# SAML21_Xplained_Pro_Target_MCU.net
KiCad netlist of a schematic drawn in Altium Designer
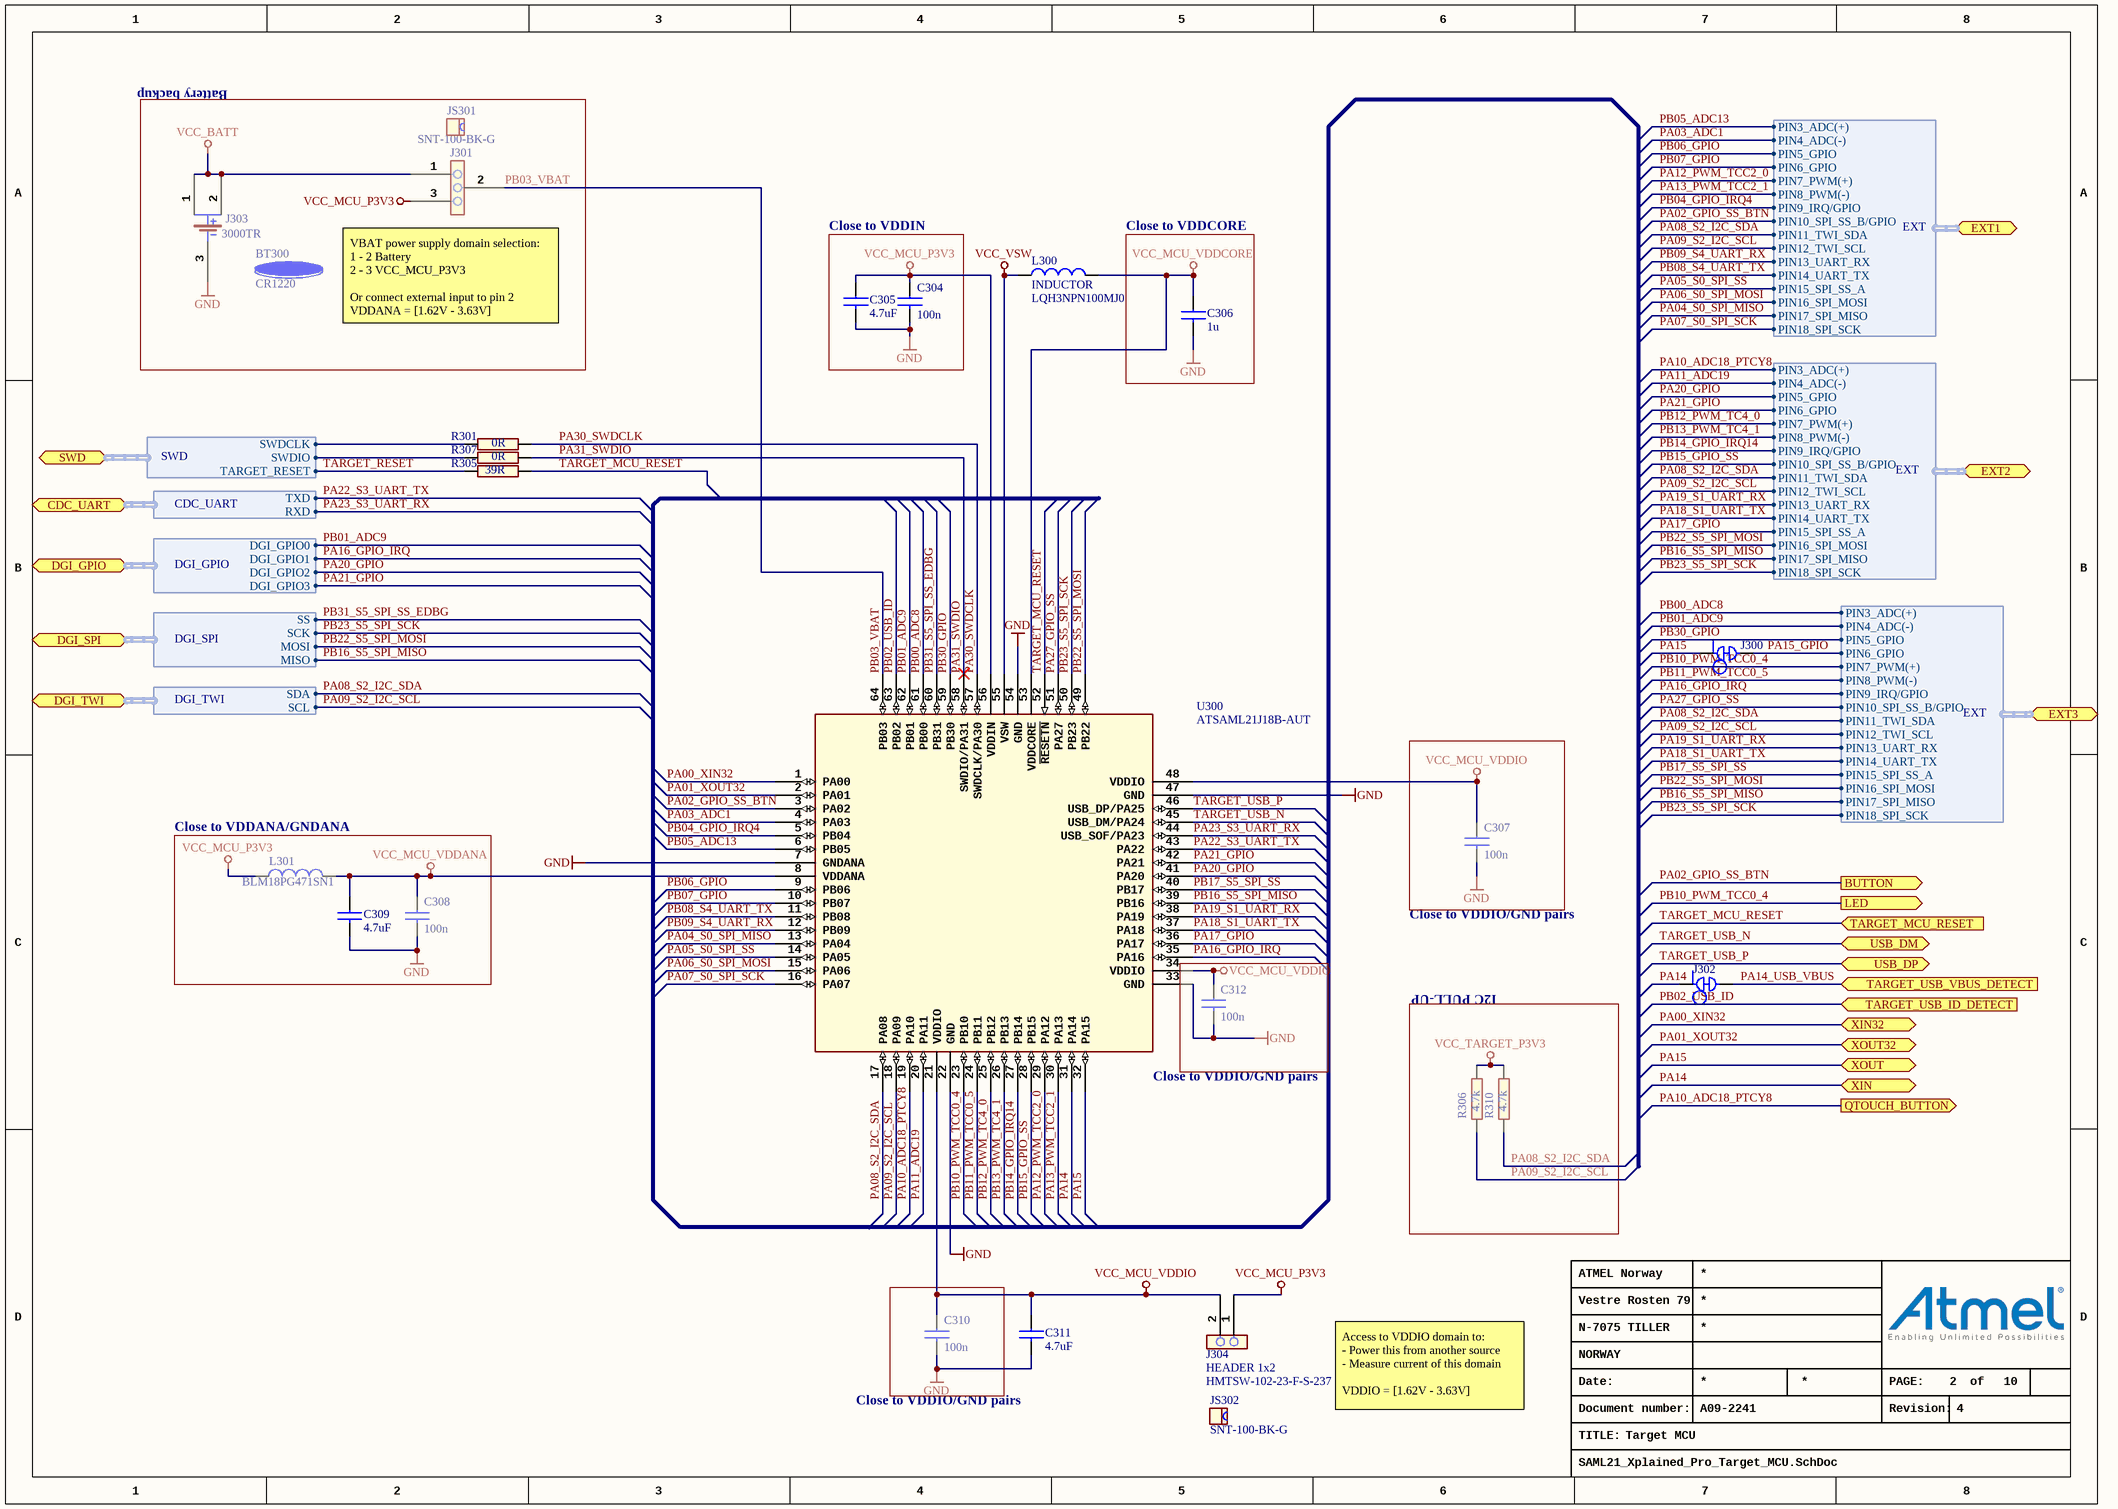
[diagram p0: SAML21_Xplained_Pro_Target_MCU.SchDoc]

(export (version "E")
  (design (tool "Eeschema 10.0.6"))
  (components
    (comp (ref "BT300")
      (value "CR1220")
      (footprint "AP9-00125")
      (description "CR1220 Lithium coin-cell battery")
      (fields (field (name "MANUFACTURER") "Panasonic") (field (name "Comment") "COIN-CELL"))
      (libsource (lib "AltiumDbLib") (part "COIN-CELL"))
    )
    (comp (ref "C304")
      (value "100n")
      (footprint "AP1-00053")
      (description "Ceramic capacitor, SMD 0402, X7R, 16V, +/-10%")
      (fields (field (name "TOLERANCE") "16V, +/-10%") (field (name "MANUFACTURER") "Kemet"))
      (libsource (lib "AltiumDbLib") (part "CAP-NONPOL"))
    )
    (comp (ref "C305")
      (value "4.7uF")
      (footprint "AP1-00117")
      (description "Ceramic capacitor, SMD 0603, X5R, 10V, 10% (de31036)")
      (fields (field (name "TOLERANCE") "10%") (field (name "MANUFACTURER") "tdk"))
      (libsource (lib "AltiumDbLib") (part "CAP-NONPOL"))
    )
    (comp (ref "C306")
      (value "1u")
      (footprint "AP1-00053")
      (description "Ceramic capacitor, SMD 0402, X5R, 6.3V, +/-10% (de26942)")
      (fields (field (name "TOLERANCE") "+/-10%") (field (name "MANUFACTURER") "Kemet"))
      (libsource (lib "AltiumDbLib") (part "CAP-NONPOL"))
    )
    (comp (ref "C307")
      (value "100n")
      (footprint "AP1-00053")
      (description "Ceramic capacitor, SMD 0402, X7R, 16V, +/-10%")
      (fields (field (name "TOLERANCE") "16V, +/-10%") (field (name "MANUFACTURER") "Kemet"))
      (libsource (lib "AltiumDbLib") (part "CAP-NONPOL"))
    )
    (comp (ref "C308")
      (value "100n")
      (footprint "AP1-00053")
      (description "Ceramic capacitor, SMD 0402, X7R, 16V, +/-10%")
      (fields (field (name "TOLERANCE") "16V, +/-10%") (field (name "MANUFACTURER") "Kemet"))
      (libsource (lib "AltiumDbLib") (part "CAP-NONPOL"))
    )
    (comp (ref "C309")
      (value "4.7uF")
      (footprint "AP1-00117")
      (description "Ceramic capacitor, SMD 0603, X5R, 10V, 10% (de31036)")
      (fields (field (name "TOLERANCE") "10%") (field (name "MANUFACTURER") "tdk"))
      (libsource (lib "AltiumDbLib") (part "CAP-NONPOL"))
    )
    (comp (ref "C310")
      (value "100n")
      (footprint "AP1-00053")
      (description "Ceramic capacitor, SMD 0402, X7R, 16V, +/-10%")
      (fields (field (name "TOLERANCE") "16V, +/-10%") (field (name "MANUFACTURER") "Kemet"))
      (libsource (lib "AltiumDbLib") (part "CAP-NONPOL"))
    )
    (comp (ref "C311")
      (value "4.7uF")
      (footprint "AP1-00117")
      (description "Ceramic capacitor, SMD 0603, X5R, 10V, 10% (de31036)")
      (fields (field (name "TOLERANCE") "10%") (field (name "MANUFACTURER") "tdk"))
      (libsource (lib "AltiumDbLib") (part "CAP-NONPOL"))
    )
    (comp (ref "C312")
      (value "100n")
      (footprint "AP1-00053")
      (description "Ceramic capacitor, SMD 0402, X7R, 16V, +/-10%")
      (fields (field (name "TOLERANCE") "16V, +/-10%") (field (name "MANUFACTURER") "Kemet"))
      (libsource (lib "AltiumDbLib") (part "CAP-NONPOL"))
    )
    (comp (ref "J300")
      (value "~")
      (footprint "AP9-00044")
      (description "Default closed SMD strap, 0603 size")
      (libsource (lib "AltiumDbLib") (part "SMD-STRAP_CLOSED"))
    )
    (comp (ref "J301")
      (value "Same as A08-1614 but with 1mm hole for optimal reflow soldering (no misalignment of the component)")
      (footprint "AP8-00745")
      (description "1x3 pin header, 2.54mm pitch, Pin-in-Paste THM, 1mm hole")
      (fields (field (name "MANUFACTURER") "SAMTEC") (field (name "MPN") "HMTSW-103-23-F-S-237"))
      (libsource (lib "AltiumDbLib") (part "HEADER 1x3"))
    )
    (comp (ref "J302")
      (value "~")
      (footprint "AP9-00044")
      (description "Default closed SMD strap, 0603 size")
      (libsource (lib "AltiumDbLib") (part "SMD-STRAP_CLOSED"))
    )
    (comp (ref "J303")
      (value "3000TR")
      (footprint "AP8-00313")
      (description "CR1220 Li-Ion coin-cell battery clip, SMD")
      (fields (field (name "MANUFACTURER") "Keystone Corp.") (field (name "Comment") "Elfa no: 69-525-01"))
      (libsource (lib "AltiumDbLib") (part "BATTERY_CLIP"))
    )
    (comp (ref "J304")
      (value "HEADER 1x2")
      (footprint "AP8-00733")
      (description "1x2 pin header, 2.54mm pitch, Pin-in-Paste THM")
      (fields
        (field (name "ALTIUM_VALUE") "HMTSW-102-23-F-S-237")
        (field (name "MANUFACTURER") "SAMTEC")
        (field (name "MPN") "HMTSW-102-23-F-S-237")
      )
      (libsource (lib "AltiumDbLib") (part "HEADER 1x2"))
    )
    (comp (ref "JS301")
      (value "SNT-100-BK-G")
      (footprint "AP8-00525")
      (description "Jumper cap for 2.54mm pinheader")
      (fields (field (name "MANUFACTURER") "SAMTEC"))
      (libsource (lib "AltiumDbLib") (part "JUMPER_CAP"))
    )
    (comp (ref "JS302")
      (value "SNT-100-BK-G")
      (footprint "AP8-00525")
      (description "Jumper cap for 2.54mm pinheader")
      (fields (field (name "MANUFACTURER") "SAMTEC"))
      (libsource (lib "AltiumDbLib") (part "JUMPER_CAP"))
    )
    (comp (ref "L300")
      (value "INDUCTOR")
      (footprint "AP3-00115")
      (description "10uH power inductor, Isat = 560mA , Itemp = 710mA, Rdc = 0.360ohm")
      (fields
        (field (name "ALTIUM_VALUE") "LQH3NPN100MJ0")
        (field (name "MANUFACTURER") "Murata")
        (field (name "MPN") "LQH3NPN100MJ0")
      )
      (libsource (lib "AltiumDbLib") (part "INDUCTOR"))
    )
    (comp (ref "L301")
      (value "BLM18PG471SN1")
      (footprint "AP3-00005")
      (description "SMD RF inductor 0603. Z=470Ohm (@100MHz), Max R(dc)=0.65Ohm, Max current=1A")
      (fields (field (name "TOLERANCE") "±25%") (field (name "MANUFACTURER") "Murata"))
      (libsource (lib "AltiumDbLib") (part "INDUCTOR"))
    )
    (comp (ref "R301")
      (value "0R")
      (footprint "AP2-00011")
      (description "RES 0.0 OHM 1/16W 0402 SMD")
      (fields (field (name "TOLERANCE") "1 %") (field (name "MANUFACTURER") "(n/a)"))
      (libsource (lib "") (part "R2_1"))
    )
    (comp (ref "R305")
      (value "39R")
      (footprint "AP2-00011")
      (description "Thick film resistor, SMD 0402, 1/16W, 1%")
      (fields (field (name "TOLERANCE") "1 %") (field (name "Comment") "R2"))
      (libsource (lib "") (part "R2_2"))
    )
    (comp (ref "R306")
      (value "4.7k")
      (footprint "AP2-00011")
      (description "Thick film resistor, SMD 0402, 1/16W, 1%")
      (fields (field (name "TOLERANCE") "1 %") (field (name "Comment") "R2"))
      (libsource (lib "AltiumDbLib") (part "R2"))
    )
    (comp (ref "R307")
      (value "0R")
      (footprint "AP2-00011")
      (description "RES 0.0 OHM 1/16W 0402 SMD")
      (fields (field (name "TOLERANCE") "1 %") (field (name "MANUFACTURER") "(n/a)"))
      (libsource (lib "") (part "R2_1"))
    )
    (comp (ref "R310")
      (value "4.7k")
      (footprint "AP2-00011")
      (description "Thick film resistor, SMD 0402, 1/16W, 1%")
      (fields (field (name "TOLERANCE") "1 %") (field (name "Comment") "R2"))
      (libsource (lib "AltiumDbLib") (part "R2"))
    )
    (comp (ref "U300")
      (value "ATSAML21J18B-AUT")
      (footprint "AP6-00173")
      (description "Atmel 32-bit RISC MCU 64pin")
      (fields (field (name "Comment") "TQFP64"))
      (libsource (lib "AltiumDbLib") (part "SAML21J_TQFP64"))
    )
  )
  (nets
    (net (code "7") (name "/PA00_XIN32") (class "Default")
      (node (ref "U300") (pin "1") (pinfunction "PA00_1") (pintype "bidirectional"))
    )
    (net (code "8") (name "/PA01_XOUT32") (class "Default")
      (node (ref "U300") (pin "2") (pinfunction "PA01_2") (pintype "bidirectional"))
    )
    (net (code "9") (name "/PA02_GPIO_SS_BTN") (class "Default")
      (node (ref "U300") (pin "3") (pinfunction "PA02_3") (pintype "bidirectional"))
    )
    (net (code "10") (name "/PA03_ADC1") (class "Default")
      (node (ref "U300") (pin "4") (pinfunction "PA03_4") (pintype "bidirectional"))
    )
    (net (code "11") (name "/PA04_S0_SPI_MISO") (class "Default")
      (node (ref "U300") (pin "13") (pinfunction "PA04_13") (pintype "bidirectional"))
    )
    (net (code "12") (name "/PA05_S0_SPI_SS") (class "Default")
      (node (ref "U300") (pin "14") (pinfunction "PA05_14") (pintype "bidirectional"))
    )
    (net (code "13") (name "/PA06_S0_SPI_MOSI") (class "Default")
      (node (ref "U300") (pin "15") (pinfunction "PA06_15") (pintype "bidirectional"))
    )
    (net (code "14") (name "/PA07_S0_SPI_SCK") (class "Default")
      (node (ref "U300") (pin "16") (pinfunction "PA07_16") (pintype "bidirectional"))
    )
    (net (code "15") (name "/PA08_S2_I2C_SDA") (class "Default")
      (node (ref "R310") (pin "1") (pinfunction "1_1") (pintype "passive"))
      (node (ref "U300") (pin "17") (pinfunction "PA08_17") (pintype "bidirectional"))
    )
    (net (code "16") (name "/PA09_S2_I2C_SCL") (class "Default")
      (node (ref "R306") (pin "1") (pinfunction "1_1") (pintype "passive"))
      (node (ref "U300") (pin "18") (pinfunction "PA09_18") (pintype "bidirectional"))
    )
    (net (code "17") (name "/PA10_ADC18_PTCY8") (class "Default")
      (node (ref "U300") (pin "19") (pinfunction "PA10_19") (pintype "bidirectional"))
    )
    (net (code "18") (name "/PA11_ADC19") (class "Default")
      (node (ref "U300") (pin "20") (pinfunction "PA11_20") (pintype "bidirectional"))
    )
    (net (code "19") (name "/PA12_PWM_TCC2_0") (class "Default")
      (node (ref "U300") (pin "29") (pinfunction "PA12_29") (pintype "bidirectional"))
    )
    (net (code "20") (name "/PA13_PWM_TCC2_1") (class "Default")
      (node (ref "U300") (pin "30") (pinfunction "PA13_30") (pintype "bidirectional"))
    )
    (net (code "21") (name "/PA14") (class "Default")
      (node (ref "J302") (pin "1") (pinfunction "1_1") (pintype "passive"))
      (node (ref "U300") (pin "31") (pinfunction "PA14_31") (pintype "bidirectional"))
    )
    (net (code "22") (name "/PA14_USB_VBUS") (class "Default")
      (node (ref "J302") (pin "2") (pinfunction "2_2") (pintype "passive"))
    )
    (net (code "23") (name "/PA15") (class "Default")
      (node (ref "J300") (pin "1") (pinfunction "1_1") (pintype "passive"))
      (node (ref "U300") (pin "32") (pinfunction "PA15_32") (pintype "bidirectional"))
    )
    (net (code "24") (name "/PA15_GPIO") (class "Default")
      (node (ref "J300") (pin "2") (pinfunction "2_2") (pintype "passive"))
    )
    (net (code "25") (name "/PA16_GPIO_IRQ") (class "Default")
      (node (ref "U300") (pin "35") (pinfunction "PA16_35") (pintype "bidirectional"))
    )
    (net (code "26") (name "/PA17_GPIO") (class "Default")
      (node (ref "U300") (pin "36") (pinfunction "PA17_36") (pintype "bidirectional"))
    )
    (net (code "27") (name "/PA18_S1_UART_TX") (class "Default")
      (node (ref "U300") (pin "37") (pinfunction "PA18_37") (pintype "bidirectional"))
    )
    (net (code "28") (name "/PA19_S1_UART_RX") (class "Default")
      (node (ref "U300") (pin "38") (pinfunction "PA19_38") (pintype "bidirectional"))
    )
    (net (code "29") (name "/PA20_GPIO") (class "Default")
      (node (ref "U300") (pin "41") (pinfunction "PA20_41") (pintype "bidirectional"))
    )
    (net (code "30") (name "/PA21_GPIO") (class "Default")
      (node (ref "U300") (pin "42") (pinfunction "PA21_42") (pintype "bidirectional"))
    )
    (net (code "31") (name "/PA22_S3_UART_TX") (class "Default")
      (node (ref "U300") (pin "43") (pinfunction "PA22_43") (pintype "bidirectional"))
    )
    (net (code "32") (name "/PA23_S3_UART_RX") (class "Default")
      (node (ref "U300") (pin "44") (pinfunction "USB_SOF/PA23_44") (pintype "bidirectional"))
    )
    (net (code "33") (name "/PA27_GPIO_SS") (class "Default")
      (node (ref "U300") (pin "51") (pinfunction "PA27_51") (pintype "bidirectional"))
    )
    (net (code "34") (name "/PA30_SWDCLK") (class "Default")
      (node (ref "R301") (pin "1") (pinfunction "1_1") (pintype "passive"))
      (node (ref "U300") (pin "57") (pinfunction "SWDCLK/PA30_57") (pintype "bidirectional"))
    )
    (net (code "35") (name "/PA31_SWDIO") (class "Default")
      (node (ref "R307") (pin "1") (pinfunction "1_1") (pintype "passive"))
      (node (ref "U300") (pin "58") (pinfunction "SWDIO/PA31_58") (pintype "bidirectional"))
    )
    (net (code "36") (name "/PB00_ADC8") (class "Default")
      (node (ref "U300") (pin "61") (pinfunction "PB00_61") (pintype "bidirectional"))
    )
    (net (code "37") (name "/PB01_ADC9") (class "Default")
      (node (ref "U300") (pin "62") (pinfunction "PB01_62") (pintype "bidirectional"))
    )
    (net (code "38") (name "/PB02_USB_ID") (class "Default")
      (node (ref "U300") (pin "63") (pinfunction "PB02_63") (pintype "bidirectional"))
    )
    (net (code "39") (name "/PB03_VBAT") (class "Default")
      (node (ref "J301") (pin "2") (pinfunction "2_2") (pintype "passive"))
      (node (ref "U300") (pin "64") (pinfunction "PB03_64") (pintype "bidirectional"))
    )
    (net (code "40") (name "/PB04_GPIO_IRQ4") (class "Default")
      (node (ref "U300") (pin "5") (pinfunction "PB04_5") (pintype "bidirectional"))
    )
    (net (code "41") (name "/PB05_ADC13") (class "Default")
      (node (ref "U300") (pin "6") (pinfunction "PB05_6") (pintype "bidirectional"))
    )
    (net (code "42") (name "/PB06_GPIO") (class "Default")
      (node (ref "U300") (pin "9") (pinfunction "PB06_9") (pintype "bidirectional"))
    )
    (net (code "43") (name "/PB07_GPIO") (class "Default")
      (node (ref "U300") (pin "10") (pinfunction "PB07_10") (pintype "bidirectional"))
    )
    (net (code "44") (name "/PB08_S4_UART_TX") (class "Default")
      (node (ref "U300") (pin "11") (pinfunction "PB08_11") (pintype "bidirectional"))
    )
    (net (code "45") (name "/PB09_S4_UART_RX") (class "Default")
      (node (ref "U300") (pin "12") (pinfunction "PB09_12") (pintype "bidirectional"))
    )
    (net (code "46") (name "/PB10_PWM_TCC0_4") (class "Default")
      (node (ref "U300") (pin "23") (pinfunction "PB10_23") (pintype "bidirectional"))
    )
    (net (code "47") (name "/PB11_PWM_TCC0_5") (class "Default")
      (node (ref "U300") (pin "24") (pinfunction "PB11_24") (pintype "bidirectional"))
    )
    (net (code "48") (name "/PB12_PWM_TC4_0") (class "Default")
      (node (ref "U300") (pin "25") (pinfunction "PB12_25") (pintype "bidirectional"))
    )
    (net (code "49") (name "/PB13_PWM_TC4_1") (class "Default")
      (node (ref "U300") (pin "26") (pinfunction "PB13_26") (pintype "bidirectional"))
    )
    (net (code "50") (name "/PB14_GPIO_IRQ14") (class "Default")
      (node (ref "U300") (pin "27") (pinfunction "PB14_27") (pintype "bidirectional"))
    )
    (net (code "51") (name "/PB15_GPIO_SS") (class "Default")
      (node (ref "U300") (pin "28") (pinfunction "PB15_28") (pintype "bidirectional"))
    )
    (net (code "52") (name "/PB16_S5_SPI_MISO") (class "Default")
      (node (ref "U300") (pin "39") (pinfunction "PB16_39") (pintype "bidirectional"))
    )
    (net (code "53") (name "/PB17_S5_SPI_SS") (class "Default")
      (node (ref "U300") (pin "40") (pinfunction "PB17_40") (pintype "bidirectional"))
    )
    (net (code "54") (name "/PB22_S5_SPI_MOSI") (class "Default")
      (node (ref "U300") (pin "49") (pinfunction "PB22_49") (pintype "bidirectional"))
    )
    (net (code "55") (name "/PB23_S5_SPI_SCK") (class "Default")
      (node (ref "U300") (pin "50") (pinfunction "PB23_50") (pintype "bidirectional"))
    )
    (net (code "56") (name "/PB30_GPIO") (class "Default")
      (node (ref "U300") (pin "59") (pinfunction "PB30_59") (pintype "bidirectional"))
    )
    (net (code "57") (name "/PB31_S5_SPI_SS_EDBG") (class "Default")
      (node (ref "U300") (pin "60") (pinfunction "PB31_60") (pintype "bidirectional"))
    )
    (net (code "58") (name "/SWDCLK") (class "Default")
      (node (ref "R301") (pin "2") (pinfunction "2_2") (pintype "passive"))
    )
    (net (code "59") (name "/SWDIO") (class "Default")
      (node (ref "R307") (pin "2") (pinfunction "2_2") (pintype "passive"))
    )
    (net (code "60") (name "/TARGET_MCU_RESET") (class "Default")
      (node (ref "R305") (pin "2") (pinfunction "2_2") (pintype "passive"))
      (node (ref "U300") (pin "52") (pinfunction "~{RESETN}_52") (pintype "input"))
    )
    (net (code "61") (name "/TARGET_RESET") (class "Default")
      (node (ref "R305") (pin "1") (pinfunction "1_1") (pintype "passive"))
    )
    (net (code "62") (name "/TARGET_USB_N") (class "Default")
      (node (ref "U300") (pin "45") (pinfunction "USB_DM/PA24_45") (pintype "bidirectional"))
    )
    (net (code "63") (name "/TARGET_USB_P") (class "Default")
      (node (ref "U300") (pin "46") (pinfunction "USB_DP/PA25_46") (pintype "bidirectional"))
    )
    (net (code "70") (name "GND") (class "Default")
      (node (ref "C304") (pin "2") (pinfunction "2_2") (pintype "passive"))
      (node (ref "C305") (pin "2") (pinfunction "2_2") (pintype "passive"))
      (node (ref "C306") (pin "2") (pinfunction "2_2") (pintype "passive"))
      (node (ref "C307") (pin "2") (pinfunction "2_2") (pintype "passive"))
      (node (ref "C308") (pin "2") (pinfunction "2_2") (pintype "passive"))
      (node (ref "C309") (pin "2") (pinfunction "2_2") (pintype "passive"))
      (node (ref "C310") (pin "2") (pinfunction "2_2") (pintype "passive"))
      (node (ref "C311") (pin "2") (pinfunction "2_2") (pintype "passive"))
      (node (ref "C312") (pin "2") (pinfunction "2_2") (pintype "passive"))
      (node (ref "J303") (pin "3") (pinfunction "3_3") (pintype "passive"))
      (node (ref "U300") (pin "22") (pinfunction "GND_22") (pintype "power_in"))
      (node (ref "U300") (pin "33") (pinfunction "GND_33") (pintype "power_in"))
      (node (ref "U300") (pin "47") (pinfunction "GND_47") (pintype "power_in"))
      (node (ref "U300") (pin "54") (pinfunction "GND_54") (pintype "power_in"))
      (node (ref "U300") (pin "7") (pinfunction "GNDANA_7") (pintype "power_in"))
    )
    (net (code "71") (name "VCC_BATT") (class "Default")
      (node (ref "J301") (pin "1") (pinfunction "1_1") (pintype "passive"))
      (node (ref "J303") (pin "1") (pinfunction "1_1") (pintype "power_in"))
      (node (ref "J303") (pin "2") (pinfunction "2_2") (pintype "power_in"))
    )
    (net (code "72") (name "VCC_MCU_P3V3") (class "Default")
      (node (ref "C304") (pin "1") (pinfunction "1_1") (pintype "passive"))
      (node (ref "C305") (pin "1") (pinfunction "1_1") (pintype "passive"))
      (node (ref "J301") (pin "3") (pinfunction "3_3") (pintype "passive"))
      (node (ref "J304") (pin "1") (pinfunction "1_1") (pintype "passive"))
      (node (ref "L301") (pin "1") (pinfunction "1_1") (pintype "passive"))
      (node (ref "U300") (pin "56") (pinfunction "VDDIN_56") (pintype "power_in"))
    )
    (net (code "73") (name "VCC_MCU_VDDANA") (class "Default")
      (node (ref "C308") (pin "1") (pinfunction "1_1") (pintype "passive"))
      (node (ref "C309") (pin "1") (pinfunction "1_1") (pintype "passive"))
      (node (ref "L301") (pin "2") (pinfunction "2_2") (pintype "passive"))
      (node (ref "U300") (pin "8") (pinfunction "VDDANA_8") (pintype "power_in"))
    )
    (net (code "74") (name "VCC_MCU_VDDCORE") (class "Default")
      (node (ref "C306") (pin "1") (pinfunction "1_1") (pintype "passive"))
      (node (ref "L300") (pin "2") (pinfunction "2_2") (pintype "passive"))
      (node (ref "U300") (pin "53") (pinfunction "VDDCORE_53") (pintype "power_in"))
    )
    (net (code "75") (name "VCC_MCU_VDDIO") (class "Default")
      (node (ref "C307") (pin "1") (pinfunction "1_1") (pintype "passive"))
      (node (ref "C310") (pin "1") (pinfunction "1_1") (pintype "passive"))
      (node (ref "C311") (pin "1") (pinfunction "1_1") (pintype "passive"))
      (node (ref "C312") (pin "1") (pinfunction "1_1") (pintype "passive"))
      (node (ref "J304") (pin "2") (pinfunction "2_2") (pintype "passive"))
      (node (ref "U300") (pin "21") (pinfunction "VDDIO_21") (pintype "power_in"))
      (node (ref "U300") (pin "34") (pinfunction "VDDIO_34") (pintype "power_in"))
      (node (ref "U300") (pin "48") (pinfunction "VDDIO_48") (pintype "power_in"))
    )
    (net (code "76") (name "VCC_TARGET_P3V3") (class "Default")
      (node (ref "R306") (pin "2") (pinfunction "2_2") (pintype "passive"))
      (node (ref "R310") (pin "2") (pinfunction "2_2") (pintype "passive"))
    )
    (net (code "77") (name "VCC_VSW") (class "Default")
      (node (ref "L300") (pin "1") (pinfunction "1_1") (pintype "passive"))
      (node (ref "U300") (pin "55") (pinfunction "VSW_55") (pintype "power_in"))
    )
  )
)
